# schematic.net
KiCad netlist of a schematic drawn in EasyEDA
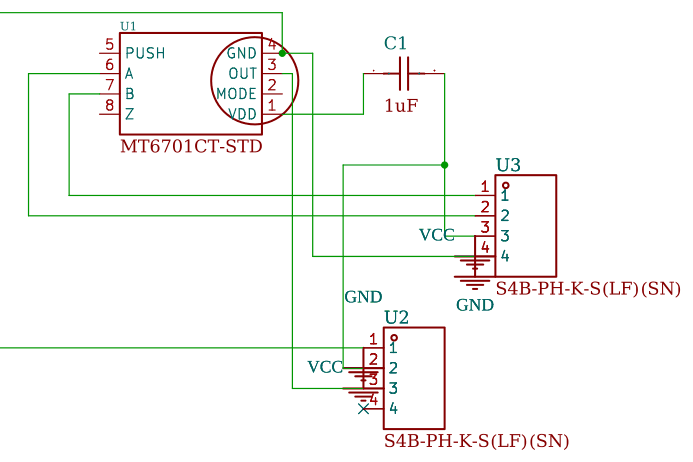
[diagram p0: schematic sheet]

(export (version "E")
  (design (tool "Eeschema 10.0.6"))
  (components
    (comp (ref "C1") (value "1uF") (libsource (lib "") (part "Unknown_695_-470")))
    (comp (ref "U1")
      (value "MT6701CT-STD")
      (fields (field (name "Manufacturer") "MagnTek(麦歌恩)"))
      (libsource (lib "") (part "Unknown_590_-465"))
    )
    (comp (ref "U2")
      (value "S4B-PH-K-S(LF)(SN)")
      (fields (field (name "Manufacturer") "JST"))
      (libsource (lib "") (part "Unknown_695_-325"))
    )
    (comp (ref "U3")
      (value "S4B-PH-K-S(LF)(SN)")
      (fields (field (name "Manufacturer") "JST"))
      (libsource (lib "") (part "Unknown_750_-400"))
    )
  )
  (nets
    (net (code "1") (name "GND") (class "Default")
      (node (ref "U1") (pin "4") (pinfunction "GND_4") (pintype "unspecified"))
      (node (ref "U2") (pin "1") (pinfunction "1_1") (pintype "unspecified"))
      (node (ref "U3") (pin "4") (pinfunction "4_4") (pintype "unspecified"))
    )
    (net (code "2") (name "Net-(U1-A)") (class "Default")
      (node (ref "U1") (pin "6") (pinfunction "A_6") (pintype "unspecified"))
      (node (ref "U3") (pin "2") (pinfunction "2_2") (pintype "unspecified"))
    )
    (net (code "3") (name "Net-(U1-B)") (class "Default")
      (node (ref "U1") (pin "7") (pinfunction "B_7") (pintype "unspecified"))
      (node (ref "U3") (pin "1") (pinfunction "1_1") (pintype "unspecified"))
    )
    (net (code "4") (name "Net-(U1-OUT)") (class "Default")
      (node (ref "U1") (pin "3") (pinfunction "OUT_3") (pintype "unspecified"))
      (node (ref "U2") (pin "3") (pinfunction "3_3") (pintype "unspecified"))
    )
    (net (code "5") (name "Net-(U1-VDD)") (class "Default")
      (node (ref "C1") (pin "1") (pinfunction "1_1") (pintype "unspecified"))
      (node (ref "U1") (pin "1") (pinfunction "VDD_1") (pintype "unspecified"))
    )
    (net (code "6") (name "VCC") (class "Default")
      (node (ref "C1") (pin "2") (pinfunction "2_2") (pintype "unspecified"))
      (node (ref "U2") (pin "2") (pinfunction "2_2") (pintype "unspecified"))
      (node (ref "U3") (pin "3") (pinfunction "3_3") (pintype "unspecified"))
    )
    (net (code "7") (name "unconnected-(U1-MODE-Pad2)") (class "Default")
      (node (ref "U1") (pin "2") (pinfunction "MODE_2") (pintype "unspecified"))
    )
    (net (code "8") (name "unconnected-(U1-PUSH-Pad5)") (class "Default")
      (node (ref "U1") (pin "5") (pinfunction "PUSH_5") (pintype "unspecified"))
    )
    (net (code "9") (name "unconnected-(U1-Z-Pad8)") (class "Default")
      (node (ref "U1") (pin "8") (pinfunction "Z_8") (pintype "unspecified"))
    )
    (net (code "10") (name "unconnected-(U2-Pad4)") (class "Default")
      (node (ref "U2") (pin "4") (pinfunction "4_4") (pintype "unspecified+no_connect"))
    )
  )
)
